# digitalky.net
KiCad netlist of a schematic drawn in EAGLE
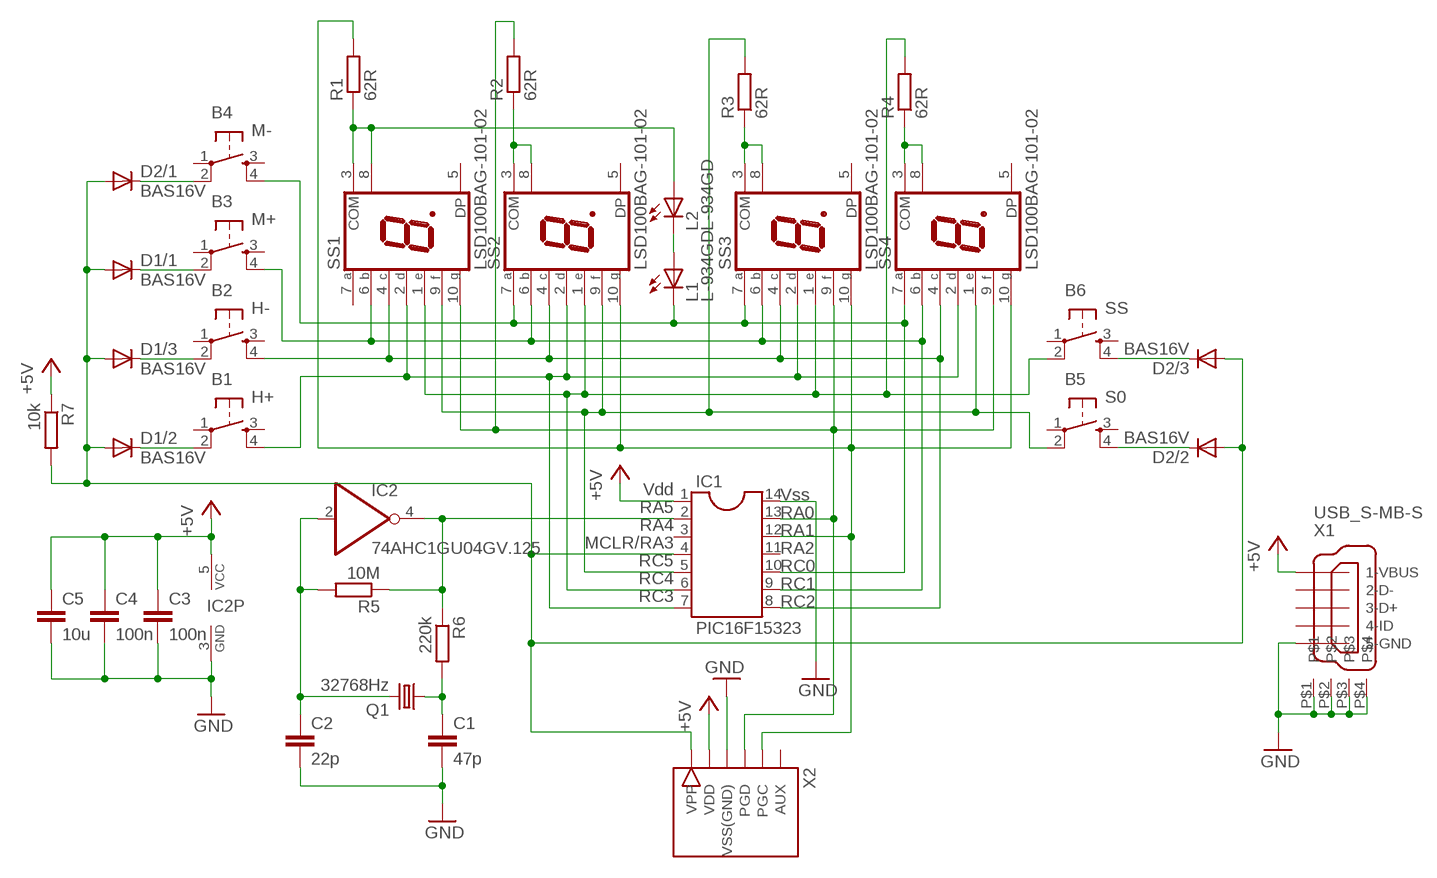
[diagram p0: schematic, sheet 1]

(export (version "E")
  (design (tool "Eeschema 10.0.6"))
  (components
    (comp (ref "B1")
      (value "H+")
      (footprint "eagle-import:TD-03")
      (libsource (lib "eagle-import") (part "TD-03"))
    )
    (comp (ref "B2")
      (value "H-")
      (footprint "eagle-import:TD-03")
      (libsource (lib "eagle-import") (part "TD-03"))
    )
    (comp (ref "B3")
      (value "M+")
      (footprint "eagle-import:TD-03")
      (libsource (lib "eagle-import") (part "TD-03"))
    )
    (comp (ref "B4")
      (value "M-")
      (footprint "eagle-import:TD-03")
      (libsource (lib "eagle-import") (part "TD-03"))
    )
    (comp (ref "B5")
      (value "S0")
      (footprint "eagle-import:TD-03")
      (libsource (lib "eagle-import") (part "TD-03"))
    )
    (comp (ref "B6")
      (value "SS")
      (footprint "eagle-import:TD-03")
      (libsource (lib "eagle-import") (part "TD-03"))
    )
    (comp (ref "C1")
      (value "47p")
      (footprint "eagle-import:C0805")
      (libsource (lib "eagle-import") (part "C-EUC0805"))
    )
    (comp (ref "C2")
      (value "22p")
      (footprint "eagle-import:C0805")
      (libsource (lib "eagle-import") (part "C-EUC0805"))
    )
    (comp (ref "C3")
      (value "100n")
      (footprint "eagle-import:C0805")
      (libsource (lib "eagle-import") (part "C-EUC0805"))
    )
    (comp (ref "C4")
      (value "100n")
      (footprint "eagle-import:C0805")
      (libsource (lib "eagle-import") (part "C-EUC0805"))
    )
    (comp (ref "C5")
      (value "10u")
      (footprint "eagle-import:C1206")
      (libsource (lib "eagle-import") (part "C-EUC1206"))
    )
    (comp (ref "D1")
      (value "BAS16V")
      (footprint "eagle-import:SOT363")
      (libsource (lib "eagle-import") (part "BAS16V"))
    )
    (comp (ref "D2")
      (value "BAS16V")
      (footprint "eagle-import:SOT363")
      (libsource (lib "eagle-import") (part "BAS16V"))
    )
    (comp (ref "IC1")
      (value "PIC16F15323")
      (footprint "eagle-import:SO-14")
      (libsource (lib "eagle-import") (part "DIL14_SMD"))
    )
    (comp (ref "IC2")
      (value "74AHC1GU04GV.125")
      (footprint "eagle-import:SOT23-5")
      (libsource (lib "eagle-import") (part "741G04DBVAHC"))
    )
    (comp (ref "L1")
      (value "L-934GD")
      (footprint "eagle-import:LED3MM")
      (libsource (lib "eagle-import") (part "LED3MM"))
    )
    (comp (ref "L2")
      (value "L-934GD")
      (footprint "eagle-import:LED3MM")
      (libsource (lib "eagle-import") (part "LED3MM"))
    )
    (comp (ref "Q1")
      (value "32768Hz")
      (footprint "eagle-import:TC38H")
      (libsource (lib "eagle-import") (part "CRYSTALTC38H"))
    )
    (comp (ref "R1")
      (value "62R")
      (footprint "eagle-import:R0805")
      (libsource (lib "eagle-import") (part "R-EU_R0805"))
    )
    (comp (ref "R2")
      (value "62R")
      (footprint "eagle-import:R0805")
      (libsource (lib "eagle-import") (part "R-EU_R0805"))
    )
    (comp (ref "R3")
      (value "62R")
      (footprint "eagle-import:R0805")
      (libsource (lib "eagle-import") (part "R-EU_R0805"))
    )
    (comp (ref "R4")
      (value "62R")
      (footprint "eagle-import:R0805")
      (libsource (lib "eagle-import") (part "R-EU_R0805"))
    )
    (comp (ref "R5")
      (value "10M")
      (footprint "eagle-import:R0805")
      (libsource (lib "eagle-import") (part "R-EU_R0805"))
    )
    (comp (ref "R6")
      (value "220k")
      (footprint "eagle-import:R0805")
      (libsource (lib "eagle-import") (part "R-EU_R0805"))
    )
    (comp (ref "R7")
      (value "10k")
      (footprint "eagle-import:R0805")
      (libsource (lib "eagle-import") (part "R-EU_R0805"))
    )
    (comp (ref "SS1")
      (value "LSD100BAG-101-02")
      (footprint "eagle-import:SA10-21")
      (libsource (lib "eagle-import") (part "7-SEG_SA10-21"))
    )
    (comp (ref "SS2")
      (value "LSD100BAG-101-02")
      (footprint "eagle-import:SA10-21")
      (libsource (lib "eagle-import") (part "7-SEG_SA10-21"))
    )
    (comp (ref "SS3")
      (value "LSD100BAG-101-02")
      (footprint "eagle-import:SA10-21")
      (libsource (lib "eagle-import") (part "7-SEG_SA10-21"))
    )
    (comp (ref "SS4")
      (value "LSD100BAG-101-02")
      (footprint "eagle-import:SA10-21")
      (libsource (lib "eagle-import") (part "7-SEG_SA10-21"))
    )
    (comp (ref "X1")
      (value "USB_S-MB-S")
      (footprint "eagle-import:USB-MB-S")
      (libsource (lib "eagle-import") (part "USB_S-MB-S"))
    )
    (comp (ref "X2")
      (value "PICKITXS")
      (footprint "eagle-import:6PIN3")
      (libsource (lib "eagle-import") (part "PICKITXS"))
    )
  )
  (nets
    (net (code "1") (name "+5V") (class "Default")
      (node (ref "C3") (pin "1") (pinfunction "1_1") (pintype "passive"))
      (node (ref "C4") (pin "1") (pinfunction "1_1") (pintype "passive"))
      (node (ref "C5") (pin "1") (pinfunction "1_1") (pintype "passive"))
      (node (ref "IC1") (pin "1") (pinfunction "1_1") (pintype "passive"))
      (node (ref "IC2") (pin "5") (pinfunction "VCC_5") (pintype "power_in"))
      (node (ref "R7") (pin "1") (pinfunction "1_1") (pintype "passive"))
      (node (ref "X1") (pin "VBUS") (pinfunction "1-VBUS_VBUS") (pintype "input"))
      (node (ref "X2") (pin "P$2") (pinfunction "VDD_P$2") (pintype "bidirectional"))
    )
    (net (code "2") (name "GND") (class "Default")
      (node (ref "C1") (pin "2") (pinfunction "2_2") (pintype "passive"))
      (node (ref "C2") (pin "2") (pinfunction "2_2") (pintype "passive"))
      (node (ref "C3") (pin "2") (pinfunction "2_2") (pintype "passive"))
      (node (ref "C4") (pin "2") (pinfunction "2_2") (pintype "passive"))
      (node (ref "C5") (pin "2") (pinfunction "2_2") (pintype "passive"))
      (node (ref "IC1") (pin "14") (pinfunction "14_14") (pintype "passive"))
      (node (ref "IC2") (pin "3") (pinfunction "GND_3") (pintype "power_in"))
      (node (ref "X1") (pin "GND") (pinfunction "5-GND_GND") (pintype "input"))
      (node (ref "X1") (pin "P$1") (pinfunction "P$1_P$1") (pintype "passive"))
      (node (ref "X1") (pin "P$2") (pinfunction "P$2_P$2") (pintype "passive"))
      (node (ref "X1") (pin "P$3") (pinfunction "P$3_P$3") (pintype "passive"))
      (node (ref "X1") (pin "P$4") (pinfunction "P$4_P$4") (pintype "passive"))
      (node (ref "X2") (pin "P$3") (pinfunction "VSS(GND)_P$3") (pintype "bidirectional"))
    )
    (net (code "3") (name "Net-(C1-Pad1)") (class "Default")
      (node (ref "C1") (pin "1") (pinfunction "1_1") (pintype "passive"))
      (node (ref "Q1") (pin "1") (pinfunction "1_1") (pintype "passive"))
      (node (ref "R6") (pin "2") (pinfunction "2_2") (pintype "passive"))
    )
    (net (code "4") (name "Net-(D1A-A)") (class "Default")
      (node (ref "D1") (pin "1") (pinfunction "A_1") (pintype "passive"))
      (node (ref "D1") (pin "2") (pinfunction "A_2") (pintype "passive"))
      (node (ref "D1") (pin "3") (pinfunction "A_3") (pintype "passive"))
      (node (ref "D2") (pin "1") (pinfunction "A_1") (pintype "passive"))
      (node (ref "D2") (pin "2") (pinfunction "A_2") (pintype "passive"))
      (node (ref "D2") (pin "3") (pinfunction "A_3") (pintype "passive"))
      (node (ref "IC1") (pin "4") (pinfunction "4_4") (pintype "passive"))
      (node (ref "R7") (pin "2") (pinfunction "2_2") (pintype "passive"))
      (node (ref "X2") (pin "P$1") (pinfunction "VPP_P$1") (pintype "bidirectional"))
    )
    (net (code "5") (name "Net-(D1A-C)") (class "Default")
      (node (ref "B3") (pin "2") (pinfunction "2_2") (pintype "passive"))
      (node (ref "D1") (pin "6") (pinfunction "C_6") (pintype "passive"))
    )
    (net (code "6") (name "Net-(D1B-C)") (class "Default")
      (node (ref "B1") (pin "2") (pinfunction "2_2") (pintype "passive"))
      (node (ref "D1") (pin "5") (pinfunction "C_5") (pintype "passive"))
    )
    (net (code "7") (name "Net-(D1C-C)") (class "Default")
      (node (ref "B2") (pin "2") (pinfunction "2_2") (pintype "passive"))
      (node (ref "D1") (pin "4") (pinfunction "C_4") (pintype "passive"))
    )
    (net (code "8") (name "Net-(D2A-C)") (class "Default")
      (node (ref "B4") (pin "2") (pinfunction "2_2") (pintype "passive"))
      (node (ref "D2") (pin "6") (pinfunction "C_6") (pintype "passive"))
    )
    (net (code "9") (name "Net-(D2B-C)") (class "Default")
      (node (ref "B5") (pin "4") (pinfunction "4_4") (pintype "passive"))
      (node (ref "D2") (pin "5") (pinfunction "C_5") (pintype "passive"))
    )
    (net (code "10") (name "Net-(D2C-C)") (class "Default")
      (node (ref "B6") (pin "4") (pinfunction "4_4") (pintype "passive"))
      (node (ref "D2") (pin "4") (pinfunction "C_4") (pintype "passive"))
    )
    (net (code "11") (name "Net-(IC2A-I)") (class "Default")
      (node (ref "C2") (pin "1") (pinfunction "1_1") (pintype "passive"))
      (node (ref "IC2") (pin "2") (pinfunction "I_2") (pintype "input"))
      (node (ref "Q1") (pin "2") (pinfunction "2_2") (pintype "passive"))
      (node (ref "R5") (pin "2") (pinfunction "2_2") (pintype "passive"))
    )
    (net (code "12") (name "Net-(IC2A-O)") (class "Default")
      (node (ref "IC1") (pin "2") (pinfunction "2_2") (pintype "passive"))
      (node (ref "IC2") (pin "4") (pinfunction "O_4") (pintype "output"))
      (node (ref "R5") (pin "1") (pinfunction "1_1") (pintype "passive"))
      (node (ref "R6") (pin "1") (pinfunction "1_1") (pintype "passive"))
    )
    (net (code "13") (name "Net-(L1-C)") (class "Default")
      (node (ref "B4") (pin "4") (pinfunction "4_4") (pintype "passive"))
      (node (ref "IC1") (pin "10") (pinfunction "10_10") (pintype "passive"))
      (node (ref "L1") (pin "K") (pinfunction "C_K") (pintype "passive"))
      (node (ref "SS2") (pin "7") (pinfunction "A_7") (pintype "passive"))
      (node (ref "SS3") (pin "7") (pinfunction "A_7") (pintype "passive"))
      (node (ref "SS4") (pin "7") (pinfunction "A_7") (pintype "passive"))
    )
    (net (code "14") (name "Net-(L2-C)") (class "Default")
      (node (ref "L1") (pin "A") (pinfunction "A_A") (pintype "passive"))
      (node (ref "L2") (pin "K") (pinfunction "C_K") (pintype "passive"))
    )
    (net (code "15") (name "Net-(L2-PadA)") (class "Default")
      (node (ref "L2") (pin "A") (pinfunction "A_A") (pintype "passive"))
      (node (ref "R1") (pin "1") (pinfunction "1_1") (pintype "passive"))
      (node (ref "SS1") (pin "3") (pinfunction "COM_3") (pintype "passive"))
      (node (ref "SS1") (pin "8") (pinfunction "COM_8") (pintype "passive"))
    )
    (net (code "16") (name "Net-(R2-Pad1)") (class "Default")
      (node (ref "R2") (pin "1") (pinfunction "1_1") (pintype "passive"))
      (node (ref "SS2") (pin "3") (pinfunction "COM_3") (pintype "passive"))
      (node (ref "SS2") (pin "8") (pinfunction "COM_8") (pintype "passive"))
    )
    (net (code "17") (name "Net-(R3-Pad1)") (class "Default")
      (node (ref "R3") (pin "1") (pinfunction "1_1") (pintype "passive"))
      (node (ref "SS3") (pin "3") (pinfunction "COM_3") (pintype "passive"))
      (node (ref "SS3") (pin "8") (pinfunction "COM_8") (pintype "passive"))
    )
    (net (code "18") (name "Net-(R4-Pad1)") (class "Default")
      (node (ref "R4") (pin "1") (pinfunction "1_1") (pintype "passive"))
      (node (ref "SS4") (pin "3") (pinfunction "COM_3") (pintype "passive"))
      (node (ref "SS4") (pin "8") (pinfunction "COM_8") (pintype "passive"))
    )
    (net (code "19") (name "Net-(SS1-B)") (class "Default")
      (node (ref "B3") (pin "4") (pinfunction "4_4") (pintype "passive"))
      (node (ref "IC1") (pin "9") (pinfunction "9_9") (pintype "passive"))
      (node (ref "SS1") (pin "6") (pinfunction "B_6") (pintype "passive"))
      (node (ref "SS2") (pin "6") (pinfunction "B_6") (pintype "passive"))
      (node (ref "SS3") (pin "6") (pinfunction "B_6") (pintype "passive"))
      (node (ref "SS4") (pin "6") (pinfunction "B_6") (pintype "passive"))
    )
    (net (code "20") (name "Net-(SS1-C)") (class "Default")
      (node (ref "B2") (pin "4") (pinfunction "4_4") (pintype "passive"))
      (node (ref "IC1") (pin "8") (pinfunction "8_8") (pintype "passive"))
      (node (ref "SS1") (pin "4") (pinfunction "C_4") (pintype "passive"))
      (node (ref "SS2") (pin "4") (pinfunction "C_4") (pintype "passive"))
      (node (ref "SS3") (pin "4") (pinfunction "C_4") (pintype "passive"))
      (node (ref "SS4") (pin "4") (pinfunction "C_4") (pintype "passive"))
    )
    (net (code "21") (name "Net-(SS1-D)") (class "Default")
      (node (ref "B1") (pin "4") (pinfunction "4_4") (pintype "passive"))
      (node (ref "IC1") (pin "7") (pinfunction "7_7") (pintype "passive"))
      (node (ref "SS1") (pin "2") (pinfunction "D_2") (pintype "passive"))
      (node (ref "SS2") (pin "2") (pinfunction "D_2") (pintype "passive"))
      (node (ref "SS3") (pin "2") (pinfunction "D_2") (pintype "passive"))
      (node (ref "SS4") (pin "2") (pinfunction "D_2") (pintype "passive"))
    )
    (net (code "22") (name "Net-(SS1-E)") (class "Default")
      (node (ref "B6") (pin "2") (pinfunction "2_2") (pintype "passive"))
      (node (ref "IC1") (pin "6") (pinfunction "6_6") (pintype "passive"))
      (node (ref "R4") (pin "2") (pinfunction "2_2") (pintype "passive"))
      (node (ref "SS1") (pin "1") (pinfunction "E_1") (pintype "passive"))
      (node (ref "SS2") (pin "1") (pinfunction "E_1") (pintype "passive"))
      (node (ref "SS3") (pin "1") (pinfunction "E_1") (pintype "passive"))
    )
    (net (code "23") (name "Net-(SS1-F)") (class "Default")
      (node (ref "B5") (pin "2") (pinfunction "2_2") (pintype "passive"))
      (node (ref "IC1") (pin "5") (pinfunction "5_5") (pintype "passive"))
      (node (ref "R3") (pin "2") (pinfunction "2_2") (pintype "passive"))
      (node (ref "SS1") (pin "9") (pinfunction "F_9") (pintype "passive"))
      (node (ref "SS2") (pin "9") (pinfunction "F_9") (pintype "passive"))
      (node (ref "SS4") (pin "1") (pinfunction "E_1") (pintype "passive"))
    )
    (net (code "24") (name "Net-(SS1-G)") (class "Default")
      (node (ref "IC1") (pin "13") (pinfunction "13_13") (pintype "passive"))
      (node (ref "R2") (pin "2") (pinfunction "2_2") (pintype "passive"))
      (node (ref "SS1") (pin "10") (pinfunction "G_10") (pintype "passive"))
      (node (ref "SS3") (pin "9") (pinfunction "F_9") (pintype "passive"))
      (node (ref "SS4") (pin "9") (pinfunction "F_9") (pintype "passive"))
      (node (ref "X2") (pin "P$4") (pinfunction "PGD_P$4") (pintype "bidirectional"))
    )
    (net (code "25") (name "Net-(SS2-G)") (class "Default")
      (node (ref "IC1") (pin "12") (pinfunction "12_12") (pintype "passive"))
      (node (ref "R1") (pin "2") (pinfunction "2_2") (pintype "passive"))
      (node (ref "SS2") (pin "10") (pinfunction "G_10") (pintype "passive"))
      (node (ref "SS3") (pin "10") (pinfunction "G_10") (pintype "passive"))
      (node (ref "SS4") (pin "10") (pinfunction "G_10") (pintype "passive"))
      (node (ref "X2") (pin "P$5") (pinfunction "PGC_P$5") (pintype "bidirectional"))
    )
    (net (code "26") (name "unconnected-(B1-Pad1)") (class "Default")
      (node (ref "B1") (pin "1") (pinfunction "1_1") (pintype "passive"))
    )
    (net (code "27") (name "unconnected-(B1-Pad3)") (class "Default")
      (node (ref "B1") (pin "3") (pinfunction "3_3") (pintype "passive"))
    )
    (net (code "28") (name "unconnected-(B2-Pad1)") (class "Default")
      (node (ref "B2") (pin "1") (pinfunction "1_1") (pintype "passive"))
    )
    (net (code "29") (name "unconnected-(B2-Pad3)") (class "Default")
      (node (ref "B2") (pin "3") (pinfunction "3_3") (pintype "passive"))
    )
    (net (code "30") (name "unconnected-(B3-Pad1)") (class "Default")
      (node (ref "B3") (pin "1") (pinfunction "1_1") (pintype "passive"))
    )
    (net (code "31") (name "unconnected-(B3-Pad3)") (class "Default")
      (node (ref "B3") (pin "3") (pinfunction "3_3") (pintype "passive"))
    )
    (net (code "32") (name "unconnected-(B4-Pad1)") (class "Default")
      (node (ref "B4") (pin "1") (pinfunction "1_1") (pintype "passive"))
    )
    (net (code "33") (name "unconnected-(B4-Pad3)") (class "Default")
      (node (ref "B4") (pin "3") (pinfunction "3_3") (pintype "passive"))
    )
    (net (code "34") (name "unconnected-(B5-Pad1)") (class "Default")
      (node (ref "B5") (pin "1") (pinfunction "1_1") (pintype "passive"))
    )
    (net (code "35") (name "unconnected-(B5-Pad3)") (class "Default")
      (node (ref "B5") (pin "3") (pinfunction "3_3") (pintype "passive"))
    )
    (net (code "36") (name "unconnected-(B6-Pad1)") (class "Default")
      (node (ref "B6") (pin "1") (pinfunction "1_1") (pintype "passive"))
    )
    (net (code "37") (name "unconnected-(B6-Pad3)") (class "Default")
      (node (ref "B6") (pin "3") (pinfunction "3_3") (pintype "passive"))
    )
    (net (code "38") (name "unconnected-(IC1-Pad3)") (class "Default")
      (node (ref "IC1") (pin "3") (pinfunction "3_3") (pintype "passive"))
    )
    (net (code "39") (name "unconnected-(IC1-Pad11)") (class "Default")
      (node (ref "IC1") (pin "11") (pinfunction "11_11") (pintype "passive"))
    )
    (net (code "40") (name "unconnected-(SS1-A-Pad7)") (class "Default")
      (node (ref "SS1") (pin "7") (pinfunction "A_7") (pintype "passive"))
    )
    (net (code "41") (name "unconnected-(SS1-DP-Pad5)") (class "Default")
      (node (ref "SS1") (pin "5") (pinfunction "DP_5") (pintype "passive"))
    )
    (net (code "42") (name "unconnected-(SS2-DP-Pad5)") (class "Default")
      (node (ref "SS2") (pin "5") (pinfunction "DP_5") (pintype "passive"))
    )
    (net (code "43") (name "unconnected-(SS3-DP-Pad5)") (class "Default")
      (node (ref "SS3") (pin "5") (pinfunction "DP_5") (pintype "passive"))
    )
    (net (code "44") (name "unconnected-(SS4-DP-Pad5)") (class "Default")
      (node (ref "SS4") (pin "5") (pinfunction "DP_5") (pintype "passive"))
    )
    (net (code "45") (name "unconnected-(X1-2-D--PadD-)") (class "Default")
      (node (ref "X1") (pin "D-") (pinfunction "2-D-_D-") (pintype "input"))
    )
    (net (code "46") (name "unconnected-(X1-3-D+-PadD+)") (class "Default")
      (node (ref "X1") (pin "D+") (pinfunction "3-D+_D+") (pintype "input"))
    )
    (net (code "47") (name "unconnected-(X1-4-ID-PadID)") (class "Default")
      (node (ref "X1") (pin "ID") (pinfunction "4-ID_ID") (pintype "input"))
    )
    (net (code "48") (name "unconnected-(X2-AUX-PadP$6)") (class "Default")
      (node (ref "X2") (pin "P$6") (pinfunction "AUX_P$6") (pintype "bidirectional"))
    )
  )
)
